# 09_Antenna.net
KiCad netlist of a schematic drawn in Altium Designer
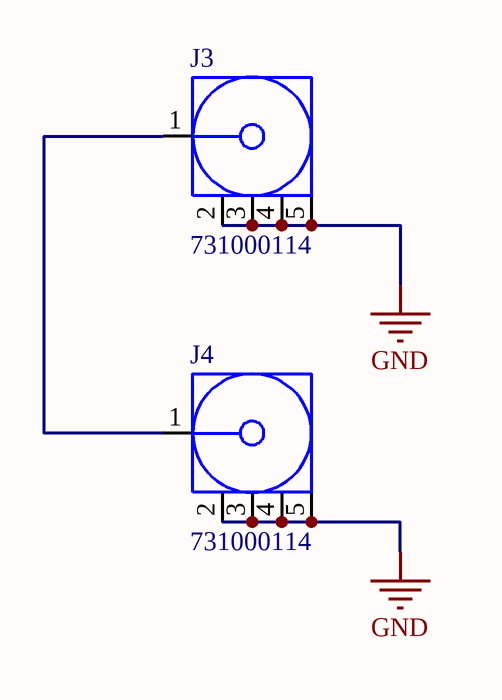
[diagram p0: 09_Antenna.SchDoc]

(export (version "E")
  (design (tool "Eeschema 10.0.6"))
  (components
    (comp (ref "J3")
      (value "731000114")
      (footprint "MOLX-731000114_V")
      (description "SMA Right-Angle PCB Jack Receptacle, Brass Body, Gold Plated, 50 Ohm, 5-Pin THD, RoHS, Tray")
      (fields (field (name "MANUFACTURER") "Molex"))
      (libsource (lib "Altium Content Vault") (part "CN-S-4F-RF5"))
    )
    (comp (ref "J4")
      (value "731000114")
      (footprint "MOLX-731000114_V")
      (description "SMA Right-Angle PCB Jack Receptacle, Brass Body, Gold Plated, 50 Ohm, 5-Pin THD, RoHS, Tray")
      (fields (field (name "MANUFACTURER") "Molex"))
      (libsource (lib "Altium Content Vault") (part "CN-S-4F-RF5"))
    )
  )
  (nets
    (net (code "1") (name "GND") (class "Default")
      (node (ref "J3") (pin "2") (pinfunction "2_2") (pintype "passive"))
      (node (ref "J3") (pin "3") (pinfunction "3_3") (pintype "passive"))
      (node (ref "J3") (pin "4") (pinfunction "4_4") (pintype "passive"))
      (node (ref "J3") (pin "5") (pinfunction "5_5") (pintype "passive"))
      (node (ref "J4") (pin "2") (pinfunction "2_2") (pintype "passive"))
      (node (ref "J4") (pin "3") (pinfunction "3_3") (pintype "passive"))
      (node (ref "J4") (pin "4") (pinfunction "4_4") (pintype "passive"))
      (node (ref "J4") (pin "5") (pinfunction "5_5") (pintype "passive"))
    )
    (net (code "2") (name "Net-(J3-Pad1)") (class "Default")
      (node (ref "J3") (pin "1") (pinfunction "1_1") (pintype "passive"))
      (node (ref "J4") (pin "1") (pinfunction "1_1") (pintype "passive"))
    )
  )
)
